# gba_link.net
KiCad netlist of a schematic drawn in EAGLE
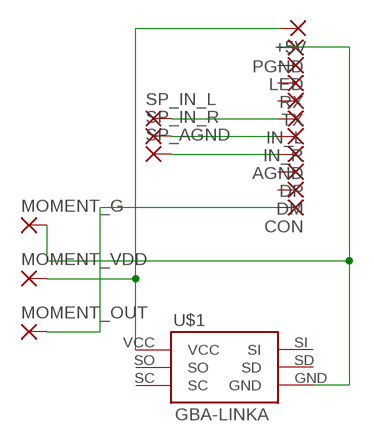
[diagram p0: schematic, sheet 1]

(export (version "E")
  (design (tool "Eeschema 10.0.6"))
  (components
    (comp (ref "+5V")
      (value "SMD2")
      (footprint "eagle-import:SMD1,27-2,54")
      (libsource (lib "eagle-import") (part "SMD2"))
    )
    (comp (ref "AGND")
      (value "SMD2")
      (footprint "eagle-import:SMD1,27-2,54")
      (libsource (lib "eagle-import") (part "SMD2"))
    )
    (comp (ref "CON")
      (value "SMD2")
      (footprint "eagle-import:SMD1,27-2,54")
      (libsource (lib "eagle-import") (part "SMD2"))
    )
    (comp (ref "DM")
      (value "SMD2")
      (footprint "eagle-import:SMD1,27-2,54")
      (libsource (lib "eagle-import") (part "SMD2"))
    )
    (comp (ref "DP")
      (value "SMD2")
      (footprint "eagle-import:SMD1,27-2,54")
      (libsource (lib "eagle-import") (part "SMD2"))
    )
    (comp (ref "IN_L")
      (value "SMD2")
      (footprint "eagle-import:SMD1,27-2,54")
      (libsource (lib "eagle-import") (part "SMD2"))
    )
    (comp (ref "IN_R")
      (value "SMD2")
      (footprint "eagle-import:SMD1,27-2,54")
      (libsource (lib "eagle-import") (part "SMD2"))
    )
    (comp (ref "LED")
      (value "SMD2")
      (footprint "eagle-import:SMD1,27-2,54")
      (libsource (lib "eagle-import") (part "SMD2"))
    )
    (comp (ref "MOMENT_G")
      (value "2,15/1,0")
      (footprint "eagle-import:2,15_1,0")
      (libsource (lib "eagle-import") (part "2,15/1,0"))
    )
    (comp (ref "MOMENT_OUT")
      (value "2,15/1,0")
      (footprint "eagle-import:2,15_1,0")
      (libsource (lib "eagle-import") (part "2,15/1,0"))
    )
    (comp (ref "MOMENT_VDD")
      (value "2,15/1,0")
      (footprint "eagle-import:2,15_1,0")
      (libsource (lib "eagle-import") (part "2,15/1,0"))
    )
    (comp (ref "PGND")
      (value "SMD2")
      (footprint "eagle-import:SMD1,27-2,54")
      (libsource (lib "eagle-import") (part "SMD2"))
    )
    (comp (ref "RX")
      (value "SMD2")
      (footprint "eagle-import:SMD1,27-2,54")
      (libsource (lib "eagle-import") (part "SMD2"))
    )
    (comp (ref "SP_AGND")
      (value "2,15/1,0")
      (footprint "eagle-import:2,15_1,0")
      (libsource (lib "eagle-import") (part "2,15/1,0"))
    )
    (comp (ref "SP_IN_L")
      (value "2,15/1,0")
      (footprint "eagle-import:2,15_1,0")
      (libsource (lib "eagle-import") (part "2,15/1,0"))
    )
    (comp (ref "SP_IN_R")
      (value "2,15/1,0")
      (footprint "eagle-import:2,15_1,0")
      (libsource (lib "eagle-import") (part "2,15/1,0"))
    )
    (comp (ref "TX")
      (value "SMD2")
      (footprint "eagle-import:SMD1,27-2,54")
      (libsource (lib "eagle-import") (part "SMD2"))
    )
    (comp (ref "U$1")
      (value "GBA-LINKA")
      (footprint "eagle-import:GBA-LINK-ALT")
      (libsource (lib "eagle-import") (part "GBA-LINKA"))
    )
  )
  (nets
    (net (code "1") (name "Net-(+5V-P)") (class "Default")
      (node (ref "+5V") (pin "1") (pinfunction "P_1") (pintype "passive"))
      (node (ref "MOMENT_VDD") (pin "1") (pinfunction "P_1") (pintype "passive"))
      (node (ref "U$1") (pin "VCC") (pinfunction "VCC_VCC") (pintype "bidirectional"))
    )
    (net (code "2") (name "Net-(AGND-P)") (class "Default")
      (node (ref "AGND") (pin "1") (pinfunction "P_1") (pintype "passive"))
      (node (ref "SP_AGND") (pin "1") (pinfunction "P_1") (pintype "passive"))
    )
    (net (code "3") (name "Net-(CON-P)") (class "Default")
      (node (ref "CON") (pin "1") (pinfunction "P_1") (pintype "passive"))
      (node (ref "MOMENT_OUT") (pin "1") (pinfunction "P_1") (pintype "passive"))
    )
    (net (code "4") (name "Net-(IN_L-P)") (class "Default")
      (node (ref "IN_L") (pin "1") (pinfunction "P_1") (pintype "passive"))
      (node (ref "SP_IN_L") (pin "1") (pinfunction "P_1") (pintype "passive"))
    )
    (net (code "5") (name "Net-(IN_R-P)") (class "Default")
      (node (ref "IN_R") (pin "1") (pinfunction "P_1") (pintype "passive"))
      (node (ref "SP_IN_R") (pin "1") (pinfunction "P_1") (pintype "passive"))
    )
    (net (code "6") (name "Net-(MOMENT_G-P)") (class "Default")
      (node (ref "MOMENT_G") (pin "1") (pinfunction "P_1") (pintype "passive"))
      (node (ref "PGND") (pin "1") (pinfunction "P_1") (pintype "passive"))
      (node (ref "U$1") (pin "GND") (pinfunction "GND_GND") (pintype "bidirectional"))
    )
    (net (code "7") (name "unconnected-(DM-P-Pad1)") (class "Default")
      (node (ref "DM") (pin "1") (pinfunction "P_1") (pintype "passive"))
    )
    (net (code "8") (name "unconnected-(DP-P-Pad1)") (class "Default")
      (node (ref "DP") (pin "1") (pinfunction "P_1") (pintype "passive"))
    )
    (net (code "9") (name "unconnected-(LED-P-Pad1)") (class "Default")
      (node (ref "LED") (pin "1") (pinfunction "P_1") (pintype "passive"))
    )
    (net (code "10") (name "unconnected-(RX-P-Pad1)") (class "Default")
      (node (ref "RX") (pin "1") (pinfunction "P_1") (pintype "passive"))
    )
    (net (code "11") (name "unconnected-(TX-P-Pad1)") (class "Default")
      (node (ref "TX") (pin "1") (pinfunction "P_1") (pintype "passive"))
    )
    (net (code "12") (name "unconnected-(U$1-PadSC)") (class "Default")
      (node (ref "U$1") (pin "SC") (pinfunction "SC_SC") (pintype "bidirectional"))
    )
    (net (code "13") (name "unconnected-(U$1-PadSD)") (class "Default")
      (node (ref "U$1") (pin "SD") (pinfunction "SD_SD") (pintype "bidirectional"))
    )
    (net (code "14") (name "unconnected-(U$1-PadSI)") (class "Default")
      (node (ref "U$1") (pin "SI") (pinfunction "SI_SI") (pintype "bidirectional"))
    )
    (net (code "15") (name "unconnected-(U$1-PadSO)") (class "Default")
      (node (ref "U$1") (pin "SO") (pinfunction "SO_SO") (pintype "bidirectional"))
    )
  )
)
